# MS3100_MCU_V0_1.net
KiCad netlist of a schematic drawn in Altium Designer
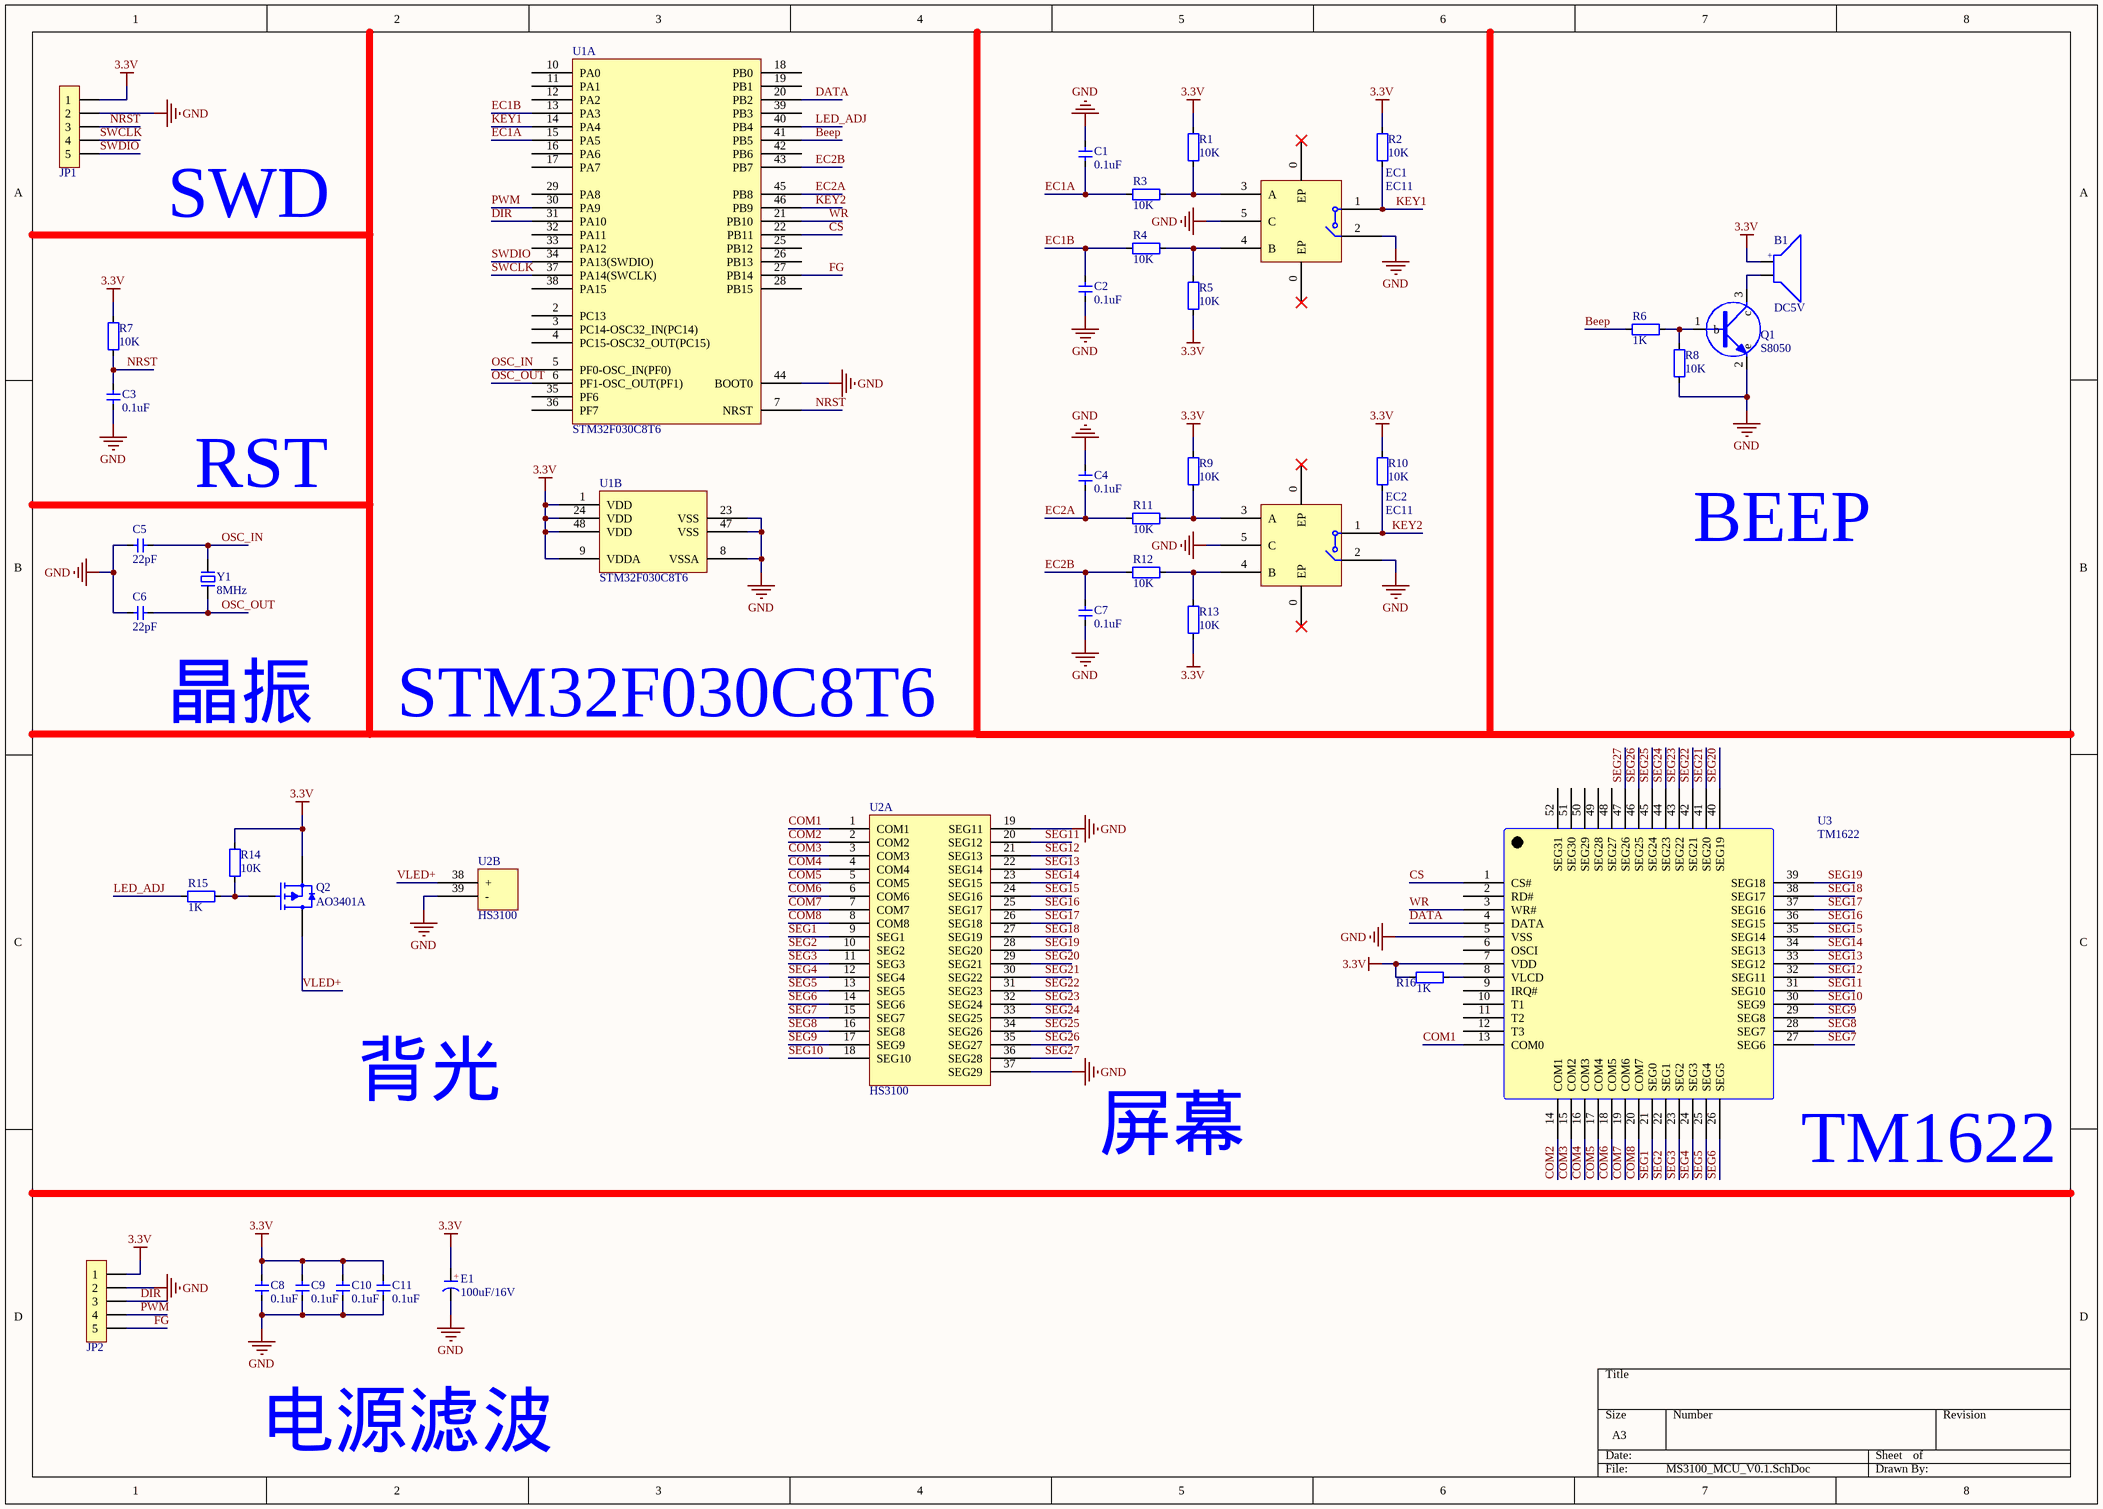
[diagram p0: MS3100_MCU_V0.1.SchDoc]

(export (version "E")
  (design (tool "Eeschema 10.0.6"))
  (components
    (comp (ref "B1")
      (value "DC5V")
      (footprint "BEEP 7.6X12X7.5")
      (description "蜂鸣器")
      (fields (field (name "版权归属") "源创客"))
      (libsource (lib "模块器件") (part "BEEP"))
    )
    (comp (ref "C1")
      (value "0.1uF")
      (footprint "C 0603")
      (description "无极性贴片电容")
      (fields (field (name "版权归属") "源创客"))
      (libsource (lib "电容") (part "C"))
    )
    (comp (ref "C2")
      (value "0.1uF")
      (footprint "C 0603")
      (description "无极性贴片电容")
      (fields (field (name "版权归属") "源创客"))
      (libsource (lib "电容") (part "C"))
    )
    (comp (ref "C3")
      (value "0.1uF")
      (footprint "C 0603")
      (description "无极性贴片电容")
      (fields (field (name "版权归属") "源创客"))
      (libsource (lib "电容") (part "C"))
    )
    (comp (ref "C4")
      (value "0.1uF")
      (footprint "C 0603")
      (description "无极性贴片电容")
      (fields (field (name "版权归属") "源创客"))
      (libsource (lib "电容") (part "C"))
    )
    (comp (ref "C5")
      (value "22pF")
      (footprint "C 0603")
      (description "无极性贴片电容")
      (fields (field (name "版权归属") "源创客"))
      (libsource (lib "电容") (part "C"))
    )
    (comp (ref "C6")
      (value "22pF")
      (footprint "C 0603")
      (description "无极性贴片电容")
      (fields (field (name "版权归属") "源创客"))
      (libsource (lib "电容") (part "C"))
    )
    (comp (ref "C7")
      (value "0.1uF")
      (footprint "C 0603")
      (description "无极性贴片电容")
      (fields (field (name "版权归属") "源创客"))
      (libsource (lib "电容") (part "C"))
    )
    (comp (ref "C8")
      (value "0.1uF")
      (footprint "C 0603")
      (description "无极性贴片电容")
      (fields (field (name "版权归属") "源创客"))
      (libsource (lib "电容") (part "C"))
    )
    (comp (ref "C9")
      (value "0.1uF")
      (footprint "C 0603")
      (description "无极性贴片电容")
      (fields (field (name "版权归属") "源创客"))
      (libsource (lib "电容") (part "C"))
    )
    (comp (ref "C10")
      (value "0.1uF")
      (footprint "C 0603")
      (description "无极性贴片电容")
      (fields (field (name "版权归属") "源创客"))
      (libsource (lib "电容") (part "C"))
    )
    (comp (ref "C11")
      (value "0.1uF")
      (footprint "C 0603")
      (description "无极性贴片电容")
      (fields (field (name "版权归属") "源创客"))
      (libsource (lib "电容") (part "C"))
    )
    (comp (ref "E1")
      (value "100uF/16V")
      (footprint "CAP 2.0*5*11 - BK")
      (description "直插电解电容")
      (fields (field (name "版权归属") "源创客"))
      (libsource (lib "电容") (part "C-CAP"))
    )
    (comp (ref "EC1")
      (value "EC11")
      (footprint "EC11A")
      (description "旋钮电位器")
      (libsource (lib "电位器") (part "EC11"))
    )
    (comp (ref "EC2")
      (value "EC11")
      (footprint "EC11A")
      (description "旋钮电位器")
      (libsource (lib "电位器") (part "EC11"))
    )
    (comp (ref "JP1")
      (value "HDR-1X5")
      (footprint "SWD_JOANLAB")
      (description "5P接插件")
      (fields (field (name "版权归属") "源创客"))
      (libsource (lib "排针-排母") (part "Header 5"))
    )
    (comp (ref "JP2")
      (value "HDR-1X5")
      (footprint "XH2.54-5P")
      (description "5P接插件")
      (fields (field (name "版权归属") "源创客"))
      (libsource (lib "排针-排母") (part "Header 5"))
    )
    (comp (ref "Q1") (value "S8050") (footprint "SOT23-3L") (libsource (lib "三极管") (part "NPN")))
    (comp (ref "Q2")
      (value "AO3401A")
      (footprint "SOT23-3")
      (description "P-MOS")
      (libsource (lib "三极管") (part "AO3401A"))
    )
    (comp (ref "R1")
      (value "10K")
      (footprint "R 0603")
      (description "贴片电阻")
      (fields (field (name "版权归属") "源创客"))
      (libsource (lib "电阻") (part "R"))
    )
    (comp (ref "R2")
      (value "10K")
      (footprint "R 0603")
      (description "贴片电阻")
      (fields (field (name "版权归属") "源创客"))
      (libsource (lib "电阻") (part "R"))
    )
    (comp (ref "R3")
      (value "10K")
      (footprint "R 0603")
      (description "贴片电阻")
      (fields (field (name "版权归属") "源创客"))
      (libsource (lib "") (part "R_1"))
    )
    (comp (ref "R4")
      (value "10K")
      (footprint "R 0603")
      (description "贴片电阻")
      (fields (field (name "版权归属") "源创客"))
      (libsource (lib "") (part "R_1"))
    )
    (comp (ref "R5")
      (value "10K")
      (footprint "R 0603")
      (description "贴片电阻")
      (fields (field (name "版权归属") "源创客"))
      (libsource (lib "电阻") (part "R"))
    )
    (comp (ref "R6")
      (value "1K")
      (footprint "R 0603")
      (description "贴片电阻")
      (fields (field (name "版权归属") "源创客"))
      (libsource (lib "") (part "R_1"))
    )
    (comp (ref "R7")
      (value "10K")
      (footprint "R 0603")
      (description "贴片电阻")
      (fields (field (name "版权归属") "源创客"))
      (libsource (lib "电阻") (part "R"))
    )
    (comp (ref "R8")
      (value "10K")
      (footprint "R 0603")
      (description "贴片电阻")
      (fields (field (name "版权归属") "源创客"))
      (libsource (lib "电阻") (part "R"))
    )
    (comp (ref "R9")
      (value "10K")
      (footprint "R 0603")
      (description "贴片电阻")
      (fields (field (name "版权归属") "源创客"))
      (libsource (lib "电阻") (part "R"))
    )
    (comp (ref "R10")
      (value "10K")
      (footprint "R 0603")
      (description "贴片电阻")
      (fields (field (name "版权归属") "源创客"))
      (libsource (lib "电阻") (part "R"))
    )
    (comp (ref "R11")
      (value "10K")
      (footprint "R 0603")
      (description "贴片电阻")
      (fields (field (name "版权归属") "源创客"))
      (libsource (lib "") (part "R_1"))
    )
    (comp (ref "R12")
      (value "10K")
      (footprint "R 0603")
      (description "贴片电阻")
      (fields (field (name "版权归属") "源创客"))
      (libsource (lib "") (part "R_1"))
    )
    (comp (ref "R13")
      (value "10K")
      (footprint "R 0603")
      (description "贴片电阻")
      (fields (field (name "版权归属") "源创客"))
      (libsource (lib "电阻") (part "R"))
    )
    (comp (ref "R14")
      (value "10K")
      (footprint "R 0603")
      (description "贴片电阻")
      (fields (field (name "版权归属") "源创客"))
      (libsource (lib "电阻") (part "R"))
    )
    (comp (ref "R15")
      (value "1K")
      (footprint "R 0603")
      (description "贴片电阻")
      (fields (field (name "版权归属") "源创客"))
      (libsource (lib "") (part "R_1"))
    )
    (comp (ref "R16")
      (value "1K")
      (footprint "R 0603")
      (description "贴片电阻")
      (fields (field (name "版权归属") "源创客"))
      (libsource (lib "") (part "R_1"))
    )
    (comp (ref "U1")
      (value "STM32F030C8T6")
      (footprint "STM32F030C8T6")
      (libsource (lib "STM32系列单片机") (part "STM32F030C8T6"))
    )
    (comp (ref "U2")
      (value "HS3100")
      (footprint "HS3100")
      (description "HS3100的屏幕")
      (libsource (lib "显示屏幕") (part "HS3100"))
    )
    (comp (ref "U3")
      (value "TM1622")
      (footprint "TM1622")
      (description "LCD驱动芯片，52脚")
      (libsource (lib "显示芯片") (part "TM1622"))
    )
    (comp (ref "Y1")
      (value "8MHz")
      (footprint "XTAL-49S SMD")
      (description "2脚晶振")
      (fields (field (name "版权归属") "源创客"))
      (libsource (lib "晶振") (part "XTAL-2"))
    )
  )
  (nets
    (net (code "1") (name "/Beep") (class "Default")
      (node (ref "R6") (pin "1") (pinfunction "1_1") (pintype "passive"))
      (node (ref "U1") (pin "41") (pinfunction "PB5_41") (pintype "passive"))
    )
    (net (code "2") (name "/COM1") (class "Default")
      (node (ref "U2") (pin "1") (pinfunction "COM1_1") (pintype "passive"))
      (node (ref "U3") (pin "13") (pinfunction "COM0_13") (pintype "passive"))
    )
    (net (code "3") (name "/COM2") (class "Default")
      (node (ref "U2") (pin "2") (pinfunction "COM2_2") (pintype "passive"))
      (node (ref "U3") (pin "14") (pinfunction "COM1_14") (pintype "passive"))
    )
    (net (code "4") (name "/COM3") (class "Default")
      (node (ref "U2") (pin "3") (pinfunction "COM3_3") (pintype "passive"))
      (node (ref "U3") (pin "15") (pinfunction "COM2_15") (pintype "passive"))
    )
    (net (code "5") (name "/COM4") (class "Default")
      (node (ref "U2") (pin "4") (pinfunction "COM4_4") (pintype "passive"))
      (node (ref "U3") (pin "16") (pinfunction "COM3_16") (pintype "passive"))
    )
    (net (code "6") (name "/COM5") (class "Default")
      (node (ref "U2") (pin "5") (pinfunction "COM5_5") (pintype "passive"))
      (node (ref "U3") (pin "17") (pinfunction "COM4_17") (pintype "passive"))
    )
    (net (code "7") (name "/COM6") (class "Default")
      (node (ref "U2") (pin "6") (pinfunction "COM6_6") (pintype "passive"))
      (node (ref "U3") (pin "18") (pinfunction "COM5_18") (pintype "passive"))
    )
    (net (code "8") (name "/COM7") (class "Default")
      (node (ref "U2") (pin "7") (pinfunction "COM7_7") (pintype "passive"))
      (node (ref "U3") (pin "19") (pinfunction "COM6_19") (pintype "passive"))
    )
    (net (code "9") (name "/COM8") (class "Default")
      (node (ref "U2") (pin "8") (pinfunction "COM8_8") (pintype "passive"))
      (node (ref "U3") (pin "20") (pinfunction "COM7_20") (pintype "passive"))
    )
    (net (code "10") (name "/CS") (class "Default")
      (node (ref "U1") (pin "22") (pinfunction "PB11_22") (pintype "passive"))
      (node (ref "U3") (pin "1") (pinfunction "CS#_1") (pintype "passive"))
    )
    (net (code "11") (name "/DATA") (class "Default")
      (node (ref "U1") (pin "20") (pinfunction "PB2_20") (pintype "passive"))
      (node (ref "U3") (pin "4") (pinfunction "DATA_4") (pintype "passive"))
    )
    (net (code "12") (name "/DIR") (class "Default")
      (node (ref "JP2") (pin "3") (pinfunction "3_3") (pintype "passive"))
      (node (ref "U1") (pin "31") (pinfunction "PA10_31") (pintype "passive"))
    )
    (net (code "13") (name "/EC1A") (class "Default")
      (node (ref "C1") (pin "1") (pinfunction "1_1") (pintype "passive"))
      (node (ref "R3") (pin "1") (pinfunction "1_1") (pintype "passive"))
      (node (ref "U1") (pin "15") (pinfunction "PA5_15") (pintype "passive"))
    )
    (net (code "14") (name "/EC1B") (class "Default")
      (node (ref "C2") (pin "2") (pinfunction "2_2") (pintype "passive"))
      (node (ref "R4") (pin "1") (pinfunction "1_1") (pintype "passive"))
      (node (ref "U1") (pin "13") (pinfunction "PA3_13") (pintype "passive"))
    )
    (net (code "15") (name "/EC2A") (class "Default")
      (node (ref "C4") (pin "1") (pinfunction "1_1") (pintype "passive"))
      (node (ref "R11") (pin "1") (pinfunction "1_1") (pintype "passive"))
      (node (ref "U1") (pin "45") (pinfunction "PB8_45") (pintype "passive"))
    )
    (net (code "16") (name "/EC2B") (class "Default")
      (node (ref "C7") (pin "2") (pinfunction "2_2") (pintype "passive"))
      (node (ref "R12") (pin "1") (pinfunction "1_1") (pintype "passive"))
      (node (ref "U1") (pin "43") (pinfunction "PB7_43") (pintype "passive"))
    )
    (net (code "17") (name "/FG") (class "Default")
      (node (ref "JP2") (pin "5") (pinfunction "5_5") (pintype "passive"))
      (node (ref "U1") (pin "27") (pinfunction "PB14_27") (pintype "passive"))
    )
    (net (code "18") (name "/KEY1") (class "Default")
      (node (ref "EC1") (pin "1") (pintype "passive"))
      (node (ref "R2") (pin "1") (pinfunction "1_1") (pintype "passive"))
      (node (ref "U1") (pin "14") (pinfunction "PA4_14") (pintype "passive"))
    )
    (net (code "19") (name "/KEY2") (class "Default")
      (node (ref "EC2") (pin "1") (pintype "passive"))
      (node (ref "R10") (pin "1") (pinfunction "1_1") (pintype "passive"))
      (node (ref "U1") (pin "46") (pinfunction "PB9_46") (pintype "passive"))
    )
    (net (code "20") (name "/LED_ADJ") (class "Default")
      (node (ref "R15") (pin "1") (pinfunction "1_1") (pintype "passive"))
      (node (ref "U1") (pin "40") (pinfunction "PB4_40") (pintype "passive"))
    )
    (net (code "21") (name "/NRST") (class "Default")
      (node (ref "C3") (pin "2") (pinfunction "2_2") (pintype "passive"))
      (node (ref "JP1") (pin "3") (pinfunction "3_3") (pintype "passive"))
      (node (ref "R7") (pin "1") (pinfunction "1_1") (pintype "passive"))
      (node (ref "U1") (pin "7") (pinfunction "NRST_7") (pintype "passive"))
    )
    (net (code "22") (name "/OSC_IN") (class "Default")
      (node (ref "C5") (pin "2") (pinfunction "2_2") (pintype "passive"))
      (node (ref "U1") (pin "5") (pinfunction "PF0-OSC_IN(PF0)_5") (pintype "passive"))
      (node (ref "Y1") (pin "2") (pinfunction "2_2") (pintype "passive"))
    )
    (net (code "23") (name "/OSC_OUT") (class "Default")
      (node (ref "C6") (pin "2") (pinfunction "2_2") (pintype "passive"))
      (node (ref "U1") (pin "6") (pinfunction "PF1-OSC_OUT(PF1)_6") (pintype "passive"))
      (node (ref "Y1") (pin "1") (pinfunction "1_1") (pintype "passive"))
    )
    (net (code "24") (name "/PWM") (class "Default")
      (node (ref "JP2") (pin "4") (pinfunction "4_4") (pintype "passive"))
      (node (ref "U1") (pin "30") (pinfunction "PA9_30") (pintype "passive"))
    )
    (net (code "25") (name "/SEG1") (class "Default")
      (node (ref "U2") (pin "9") (pinfunction "SEG1_9") (pintype "passive"))
      (node (ref "U3") (pin "21") (pinfunction "SEG0_21") (pintype "passive"))
    )
    (net (code "26") (name "/SEG2") (class "Default")
      (node (ref "U2") (pin "10") (pinfunction "SEG2_10") (pintype "passive"))
      (node (ref "U3") (pin "22") (pinfunction "SEG1_22") (pintype "passive"))
    )
    (net (code "27") (name "/SEG3") (class "Default")
      (node (ref "U2") (pin "11") (pinfunction "SEG3_11") (pintype "passive"))
      (node (ref "U3") (pin "23") (pinfunction "SEG2_23") (pintype "passive"))
    )
    (net (code "28") (name "/SEG4") (class "Default")
      (node (ref "U2") (pin "12") (pinfunction "SEG4_12") (pintype "passive"))
      (node (ref "U3") (pin "24") (pinfunction "SEG3_24") (pintype "passive"))
    )
    (net (code "29") (name "/SEG5") (class "Default")
      (node (ref "U2") (pin "13") (pinfunction "SEG5_13") (pintype "passive"))
      (node (ref "U3") (pin "25") (pinfunction "SEG4_25") (pintype "passive"))
    )
    (net (code "30") (name "/SEG6") (class "Default")
      (node (ref "U2") (pin "14") (pinfunction "SEG6_14") (pintype "passive"))
      (node (ref "U3") (pin "26") (pinfunction "SEG5_26") (pintype "passive"))
    )
    (net (code "31") (name "/SEG7") (class "Default")
      (node (ref "U2") (pin "15") (pinfunction "SEG7_15") (pintype "passive"))
      (node (ref "U3") (pin "27") (pinfunction "SEG6_27") (pintype "passive"))
    )
    (net (code "32") (name "/SEG8") (class "Default")
      (node (ref "U2") (pin "16") (pinfunction "SEG8_16") (pintype "passive"))
      (node (ref "U3") (pin "28") (pinfunction "SEG7_28") (pintype "passive"))
    )
    (net (code "33") (name "/SEG9") (class "Default")
      (node (ref "U2") (pin "17") (pinfunction "SEG9_17") (pintype "passive"))
      (node (ref "U3") (pin "29") (pinfunction "SEG8_29") (pintype "passive"))
    )
    (net (code "34") (name "/SEG10") (class "Default")
      (node (ref "U2") (pin "18") (pinfunction "SEG10_18") (pintype "passive"))
      (node (ref "U3") (pin "30") (pinfunction "SEG9_30") (pintype "passive"))
    )
    (net (code "35") (name "/SEG11") (class "Default")
      (node (ref "U2") (pin "20") (pinfunction "SEG12_20") (pintype "passive"))
      (node (ref "U3") (pin "31") (pinfunction "SEG10_31") (pintype "passive"))
    )
    (net (code "36") (name "/SEG12") (class "Default")
      (node (ref "U2") (pin "21") (pinfunction "SEG13_21") (pintype "passive"))
      (node (ref "U3") (pin "32") (pinfunction "SEG11_32") (pintype "passive"))
    )
    (net (code "37") (name "/SEG13") (class "Default")
      (node (ref "U2") (pin "22") (pinfunction "SEG14_22") (pintype "passive"))
      (node (ref "U3") (pin "33") (pinfunction "SEG12_33") (pintype "passive"))
    )
    (net (code "38") (name "/SEG14") (class "Default")
      (node (ref "U2") (pin "23") (pinfunction "SEG15_23") (pintype "passive"))
      (node (ref "U3") (pin "34") (pinfunction "SEG13_34") (pintype "passive"))
    )
    (net (code "39") (name "/SEG15") (class "Default")
      (node (ref "U2") (pin "24") (pinfunction "SEG16_24") (pintype "passive"))
      (node (ref "U3") (pin "35") (pinfunction "SEG14_35") (pintype "passive"))
    )
    (net (code "40") (name "/SEG16") (class "Default")
      (node (ref "U2") (pin "25") (pinfunction "SEG17_25") (pintype "passive"))
      (node (ref "U3") (pin "36") (pinfunction "SEG15_36") (pintype "passive"))
    )
    (net (code "41") (name "/SEG17") (class "Default")
      (node (ref "U2") (pin "26") (pinfunction "SEG18_26") (pintype "passive"))
      (node (ref "U3") (pin "37") (pinfunction "SEG16_37") (pintype "passive"))
    )
    (net (code "42") (name "/SEG18") (class "Default")
      (node (ref "U2") (pin "27") (pinfunction "SEG19_27") (pintype "passive"))
      (node (ref "U3") (pin "38") (pinfunction "SEG17_38") (pintype "passive"))
    )
    (net (code "43") (name "/SEG19") (class "Default")
      (node (ref "U2") (pin "28") (pinfunction "SEG20_28") (pintype "passive"))
      (node (ref "U3") (pin "39") (pinfunction "SEG18_39") (pintype "passive"))
    )
    (net (code "44") (name "/SEG20") (class "Default")
      (node (ref "U2") (pin "29") (pinfunction "SEG21_29") (pintype "passive"))
      (node (ref "U3") (pin "40") (pinfunction "SEG19_40") (pintype "passive"))
    )
    (net (code "45") (name "/SEG21") (class "Default")
      (node (ref "U2") (pin "30") (pinfunction "SEG22_30") (pintype "passive"))
      (node (ref "U3") (pin "41") (pinfunction "SEG20_41") (pintype "passive"))
    )
    (net (code "46") (name "/SEG22") (class "Default")
      (node (ref "U2") (pin "31") (pinfunction "SEG23_31") (pintype "passive"))
      (node (ref "U3") (pin "42") (pinfunction "SEG21_42") (pintype "passive"))
    )
    (net (code "47") (name "/SEG23") (class "Default")
      (node (ref "U2") (pin "32") (pinfunction "SEG24_32") (pintype "passive"))
      (node (ref "U3") (pin "43") (pinfunction "SEG22_43") (pintype "passive"))
    )
    (net (code "48") (name "/SEG24") (class "Default")
      (node (ref "U2") (pin "33") (pinfunction "SEG25_33") (pintype "passive"))
      (node (ref "U3") (pin "44") (pinfunction "SEG23_44") (pintype "passive"))
    )
    (net (code "49") (name "/SEG25") (class "Default")
      (node (ref "U2") (pin "34") (pinfunction "SEG26_34") (pintype "passive"))
      (node (ref "U3") (pin "45") (pinfunction "SEG24_45") (pintype "passive"))
    )
    (net (code "50") (name "/SEG26") (class "Default")
      (node (ref "U2") (pin "35") (pinfunction "SEG27_35") (pintype "passive"))
      (node (ref "U3") (pin "46") (pinfunction "SEG25_46") (pintype "passive"))
    )
    (net (code "51") (name "/SEG27") (class "Default")
      (node (ref "U2") (pin "36") (pinfunction "SEG28_36") (pintype "passive"))
      (node (ref "U3") (pin "47") (pinfunction "SEG26_47") (pintype "passive"))
    )
    (net (code "52") (name "/SWCLK") (class "Default")
      (node (ref "JP1") (pin "4") (pinfunction "4_4") (pintype "passive"))
      (node (ref "U1") (pin "37") (pinfunction "PA14(SWCLK)_37") (pintype "passive"))
    )
    (net (code "53") (name "/SWDIO") (class "Default")
      (node (ref "JP1") (pin "5") (pinfunction "5_5") (pintype "passive"))
      (node (ref "U1") (pin "34") (pinfunction "PA13(SWDIO)_34") (pintype "passive"))
    )
    (net (code "54") (name "/VLED+") (class "Default")
      (node (ref "Q2") (pin "3") (pinfunction "D_3") (pintype "passive"))
      (node (ref "U2") (pin "38") (pinfunction "+_38") (pintype "passive"))
    )
    (net (code "55") (name "/WR") (class "Default")
      (node (ref "U1") (pin "21") (pinfunction "PB10_21") (pintype "passive"))
      (node (ref "U3") (pin "3") (pinfunction "WR#_3") (pintype "passive"))
    )
    (net (code "56") (name "3.3V") (class "Default")
      (node (ref "B1") (pin "1") (pinfunction "1_1") (pintype "passive"))
      (node (ref "C10") (pin "2") (pinfunction "2_2") (pintype "passive"))
      (node (ref "C11") (pin "2") (pinfunction "2_2") (pintype "passive"))
      (node (ref "C8") (pin "2") (pinfunction "2_2") (pintype "passive"))
      (node (ref "C9") (pin "2") (pinfunction "2_2") (pintype "passive"))
      (node (ref "E1") (pin "1") (pinfunction "A_1") (pintype "passive"))
      (node (ref "JP1") (pin "1") (pinfunction "1_1") (pintype "passive"))
      (node (ref "JP2") (pin "1") (pinfunction "1_1") (pintype "passive"))
      (node (ref "Q2") (pin "2") (pinfunction "S_2") (pintype "passive"))
      (node (ref "R1") (pin "2") (pinfunction "2_2") (pintype "passive"))
      (node (ref "R10") (pin "2") (pinfunction "2_2") (pintype "passive"))
      (node (ref "R13") (pin "1") (pinfunction "1_1") (pintype "passive"))
      (node (ref "R14") (pin "2") (pinfunction "2_2") (pintype "passive"))
      (node (ref "R16") (pin "1") (pinfunction "1_1") (pintype "passive"))
      (node (ref "R2") (pin "2") (pinfunction "2_2") (pintype "passive"))
      (node (ref "R5") (pin "1") (pinfunction "1_1") (pintype "passive"))
      (node (ref "R7") (pin "2") (pinfunction "2_2") (pintype "passive"))
      (node (ref "R9") (pin "2") (pinfunction "2_2") (pintype "passive"))
      (node (ref "U1") (pin "1") (pinfunction "VDD_1") (pintype "passive"))
      (node (ref "U1") (pin "24") (pinfunction "VDD_24") (pintype "passive"))
      (node (ref "U1") (pin "48") (pinfunction "VDD_48") (pintype "passive"))
      (node (ref "U1") (pin "9") (pinfunction "VDDA_9") (pintype "passive"))
      (node (ref "U3") (pin "7") (pinfunction "VDD_7") (pintype "passive"))
    )
    (net (code "57") (name "GND") (class "Default")
      (node (ref "C1") (pin "2") (pinfunction "2_2") (pintype "passive"))
      (node (ref "C10") (pin "1") (pinfunction "1_1") (pintype "passive"))
      (node (ref "C11") (pin "1") (pinfunction "1_1") (pintype "passive"))
      (node (ref "C2") (pin "1") (pinfunction "1_1") (pintype "passive"))
      (node (ref "C3") (pin "1") (pinfunction "1_1") (pintype "passive"))
      (node (ref "C4") (pin "2") (pinfunction "2_2") (pintype "passive"))
      (node (ref "C5") (pin "1") (pinfunction "1_1") (pintype "passive"))
      (node (ref "C6") (pin "1") (pinfunction "1_1") (pintype "passive"))
      (node (ref "C7") (pin "1") (pinfunction "1_1") (pintype "passive"))
      (node (ref "C8") (pin "1") (pinfunction "1_1") (pintype "passive"))
      (node (ref "C9") (pin "1") (pinfunction "1_1") (pintype "passive"))
      (node (ref "E1") (pin "2") (pinfunction "K_2") (pintype "passive"))
      (node (ref "EC1") (pin "2") (pintype "passive"))
      (node (ref "EC1") (pin "5") (pinfunction "C_5") (pintype "passive"))
      (node (ref "EC2") (pin "2") (pintype "passive"))
      (node (ref "EC2") (pin "5") (pinfunction "C_5") (pintype "passive"))
      (node (ref "JP1") (pin "2") (pinfunction "2_2") (pintype "passive"))
      (node (ref "JP2") (pin "2") (pinfunction "2_2") (pintype "passive"))
      (node (ref "Q1") (pin "2") (pinfunction "e_2") (pintype "passive"))
      (node (ref "R8") (pin "1") (pinfunction "1_1") (pintype "passive"))
      (node (ref "U1") (pin "23") (pinfunction "VSS_23") (pintype "passive"))
      (node (ref "U1") (pin "44") (pinfunction "BOOT0_44") (pintype "passive"))
      (node (ref "U1") (pin "47") (pinfunction "VSS_47") (pintype "passive"))
      (node (ref "U1") (pin "8") (pinfunction "VSSA_8") (pintype "passive"))
      (node (ref "U2") (pin "19") (pinfunction "SEG11_19") (pintype "passive"))
      (node (ref "U2") (pin "37") (pinfunction "SEG29_37") (pintype "passive"))
      (node (ref "U2") (pin "39") (pinfunction "-_39") (pintype "passive"))
      (node (ref "U3") (pin "5") (pinfunction "VSS_5") (pintype "passive"))
    )
    (net (code "58") (name "Net-(EC1-A)") (class "Default")
      (node (ref "EC1") (pin "3") (pinfunction "A_3") (pintype "passive"))
      (node (ref "R1") (pin "1") (pinfunction "1_1") (pintype "passive"))
      (node (ref "R3") (pin "2") (pinfunction "2_2") (pintype "passive"))
    )
    (net (code "59") (name "Net-(EC1-B)") (class "Default")
      (node (ref "EC1") (pin "4") (pinfunction "B_4") (pintype "passive"))
      (node (ref "R4") (pin "2") (pinfunction "2_2") (pintype "passive"))
      (node (ref "R5") (pin "2") (pinfunction "2_2") (pintype "passive"))
    )
    (net (code "60") (name "Net-(EC2-A)") (class "Default")
      (node (ref "EC2") (pin "3") (pinfunction "A_3") (pintype "passive"))
      (node (ref "R11") (pin "2") (pinfunction "2_2") (pintype "passive"))
      (node (ref "R9") (pin "1") (pinfunction "1_1") (pintype "passive"))
    )
    (net (code "61") (name "Net-(EC2-B)") (class "Default")
      (node (ref "EC2") (pin "4") (pinfunction "B_4") (pintype "passive"))
      (node (ref "R12") (pin "2") (pinfunction "2_2") (pintype "passive"))
      (node (ref "R13") (pin "2") (pinfunction "2_2") (pintype "passive"))
    )
    (net (code "62") (name "Net-(Q1-b)") (class "Default")
      (node (ref "Q1") (pin "1") (pinfunction "b_1") (pintype "passive"))
      (node (ref "R6") (pin "2") (pinfunction "2_2") (pintype "passive"))
      (node (ref "R8") (pin "2") (pinfunction "2_2") (pintype "passive"))
    )
    (net (code "63") (name "Net-(Q1-c)") (class "Default")
      (node (ref "B1") (pin "2") (pinfunction "2_2") (pintype "passive"))
      (node (ref "Q1") (pin "3") (pinfunction "c_3") (pintype "passive"))
    )
    (net (code "64") (name "Net-(Q2-G)") (class "Default")
      (node (ref "Q2") (pin "1") (pinfunction "G_1") (pintype "passive"))
      (node (ref "R14") (pin "1") (pinfunction "1_1") (pintype "passive"))
      (node (ref "R15") (pin "2") (pinfunction "2_2") (pintype "passive"))
    )
    (net (code "65") (name "Net-(U3-VLCD)") (class "Default")
      (node (ref "R16") (pin "2") (pinfunction "2_2") (pintype "passive"))
      (node (ref "U3") (pin "8") (pinfunction "VLCD_8") (pintype "passive"))
    )
    (net (code "66") (name "unconnected-(EC1-EP-Pad0)") (class "Default")
      (node (ref "EC1") (pin "0") (pinfunction "EP_0") (pintype "passive+no_connect"))
    )
    (net (code "67") (name "unconnected-(EC1-EP-Pad0)_1") (class "Default")
      (node (ref "EC1") (pin "0") (pinfunction "EP_0") (pintype "passive+no_connect"))
    )
    (net (code "68") (name "unconnected-(EC2-EP-Pad0)") (class "Default")
      (node (ref "EC2") (pin "0") (pinfunction "EP_0") (pintype "passive+no_connect"))
    )
    (net (code "69") (name "unconnected-(EC2-EP-Pad0)_1") (class "Default")
      (node (ref "EC2") (pin "0") (pinfunction "EP_0") (pintype "passive+no_connect"))
    )
    (net (code "70") (name "unconnected-(U1A-PA0-Pad10)") (class "Default")
      (node (ref "U1") (pin "10") (pinfunction "PA0_10") (pintype "passive"))
    )
    (net (code "71") (name "unconnected-(U1A-PA1-Pad11)") (class "Default")
      (node (ref "U1") (pin "11") (pinfunction "PA1_11") (pintype "passive"))
    )
    (net (code "72") (name "unconnected-(U1A-PA2-Pad12)") (class "Default")
      (node (ref "U1") (pin "12") (pinfunction "PA2_12") (pintype "passive"))
    )
    (net (code "73") (name "unconnected-(U1A-PA6-Pad16)") (class "Default")
      (node (ref "U1") (pin "16") (pinfunction "PA6_16") (pintype "passive"))
    )
    (net (code "74") (name "unconnected-(U1A-PA7-Pad17)") (class "Default")
      (node (ref "U1") (pin "17") (pinfunction "PA7_17") (pintype "passive"))
    )
    (net (code "75") (name "unconnected-(U1A-PA8-Pad29)") (class "Default")
      (node (ref "U1") (pin "29") (pinfunction "PA8_29") (pintype "passive"))
    )
    (net (code "76") (name "unconnected-(U1A-PA11-Pad32)") (class "Default")
      (node (ref "U1") (pin "32") (pinfunction "PA11_32") (pintype "passive"))
    )
    (net (code "77") (name "unconnected-(U1A-PA12-Pad33)") (class "Default")
      (node (ref "U1") (pin "33") (pinfunction "PA12_33") (pintype "passive"))
    )
    (net (code "78") (name "unconnected-(U1A-PA15-Pad38)") (class "Default")
      (node (ref "U1") (pin "38") (pinfunction "PA15_38") (pintype "passive"))
    )
    (net (code "79") (name "unconnected-(U1A-PB0-Pad18)") (class "Default")
      (node (ref "U1") (pin "18") (pinfunction "PB0_18") (pintype "passive"))
    )
    (net (code "80") (name "unconnected-(U1A-PB1-Pad19)") (class "Default")
      (node (ref "U1") (pin "19") (pinfunction "PB1_19") (pintype "passive"))
    )
    (net (code "81") (name "unconnected-(U1A-PB3-Pad39)") (class "Default")
      (node (ref "U1") (pin "39") (pinfunction "PB3_39") (pintype "passive"))
    )
    (net (code "82") (name "unconnected-(U1A-PB6-Pad42)") (class "Default")
      (node (ref "U1") (pin "42") (pinfunction "PB6_42") (pintype "passive"))
    )
    (net (code "83") (name "unconnected-(U1A-PB12-Pad25)") (class "Default")
      (node (ref "U1") (pin "25") (pinfunction "PB12_25") (pintype "passive"))
    )
    (net (code "84") (name "unconnected-(U1A-PB13-Pad26)") (class "Default")
      (node (ref "U1") (pin "26") (pinfunction "PB13_26") (pintype "passive"))
    )
    (net (code "85") (name "unconnected-(U1A-PB15-Pad28)") (class "Default")
      (node (ref "U1") (pin "28") (pinfunction "PB15_28") (pintype "passive"))
    )
    (net (code "86") (name "unconnected-(U1A-PC13-Pad2)") (class "Default")
      (node (ref "U1") (pin "2") (pinfunction "PC13_2") (pintype "passive"))
    )
    (net (code "87") (name "unconnected-(U1A-PC14-OSC32_IN(PC14)-Pad3)") (class "Default")
      (node (ref "U1") (pin "3") (pinfunction "PC14-OSC32_IN(PC14)_3") (pintype "passive"))
    )
    (net (code "88") (name "unconnected-(U1A-PC15-OSC32_OUT(PC15)-Pad4)") (class "Default")
      (node (ref "U1") (pin "4") (pinfunction "PC15-OSC32_OUT(PC15)_4") (pintype "passive"))
    )
    (net (code "89") (name "unconnected-(U1A-PF6-Pad35)") (class "Default")
      (node (ref "U1") (pin "35") (pinfunction "PF6_35") (pintype "passive"))
    )
    (net (code "90") (name "unconnected-(U1A-PF7-Pad36)") (class "Default")
      (node (ref "U1") (pin "36") (pinfunction "PF7_36") (pintype "passive"))
    )
    (net (code "91") (name "unconnected-(U3-IRQ#-Pad9)") (class "Default")
      (node (ref "U3") (pin "9") (pinfunction "IRQ#_9") (pintype "passive"))
    )
    (net (code "92") (name "unconnected-(U3-OSCI-Pad6)") (class "Default")
      (node (ref "U3") (pin "6") (pinfunction "OSCI_6") (pintype "passive"))
    )
    (net (code "93") (name "unconnected-(U3-RD#-Pad2)") (class "Default")
      (node (ref "U3") (pin "2") (pinfunction "RD#_2") (pintype "passive"))
    )
    (net (code "94") (name "unconnected-(U3-SEG27-Pad48)") (class "Default")
      (node (ref "U3") (pin "48") (pinfunction "SEG27_48") (pintype "passive"))
    )
    (net (code "95") (name "unconnected-(U3-SEG28-Pad49)") (class "Default")
      (node (ref "U3") (pin "49") (pinfunction "SEG28_49") (pintype "passive"))
    )
    (net (code "96") (name "unconnected-(U3-SEG29-Pad50)") (class "Default")
      (node (ref "U3") (pin "50") (pinfunction "SEG29_50") (pintype "passive"))
    )
    (net (code "97") (name "unconnected-(U3-SEG30-Pad51)") (class "Default")
      (node (ref "U3") (pin "51") (pinfunction "SEG30_51") (pintype "passive"))
    )
    (net (code "98") (name "unconnected-(U3-SEG31-Pad52)") (class "Default")
      (node (ref "U3") (pin "52") (pinfunction "SEG31_52") (pintype "passive"))
    )
    (net (code "99") (name "unconnected-(U3-T1-Pad10)") (class "Default")
      (node (ref "U3") (pin "10") (pinfunction "T1_10") (pintype "passive"))
    )
    (net (code "100") (name "unconnected-(U3-T2-Pad11)") (class "Default")
      (node (ref "U3") (pin "11") (pinfunction "T2_11") (pintype "passive"))
    )
    (net (code "101") (name "unconnected-(U3-T3-Pad12)") (class "Default")
      (node (ref "U3") (pin "12") (pinfunction "T3_12") (pintype "passive"))
    )
  )
)
